# OpenEVSE_PLUS_v2_1.net
KiCad netlist of a schematic drawn in EAGLE
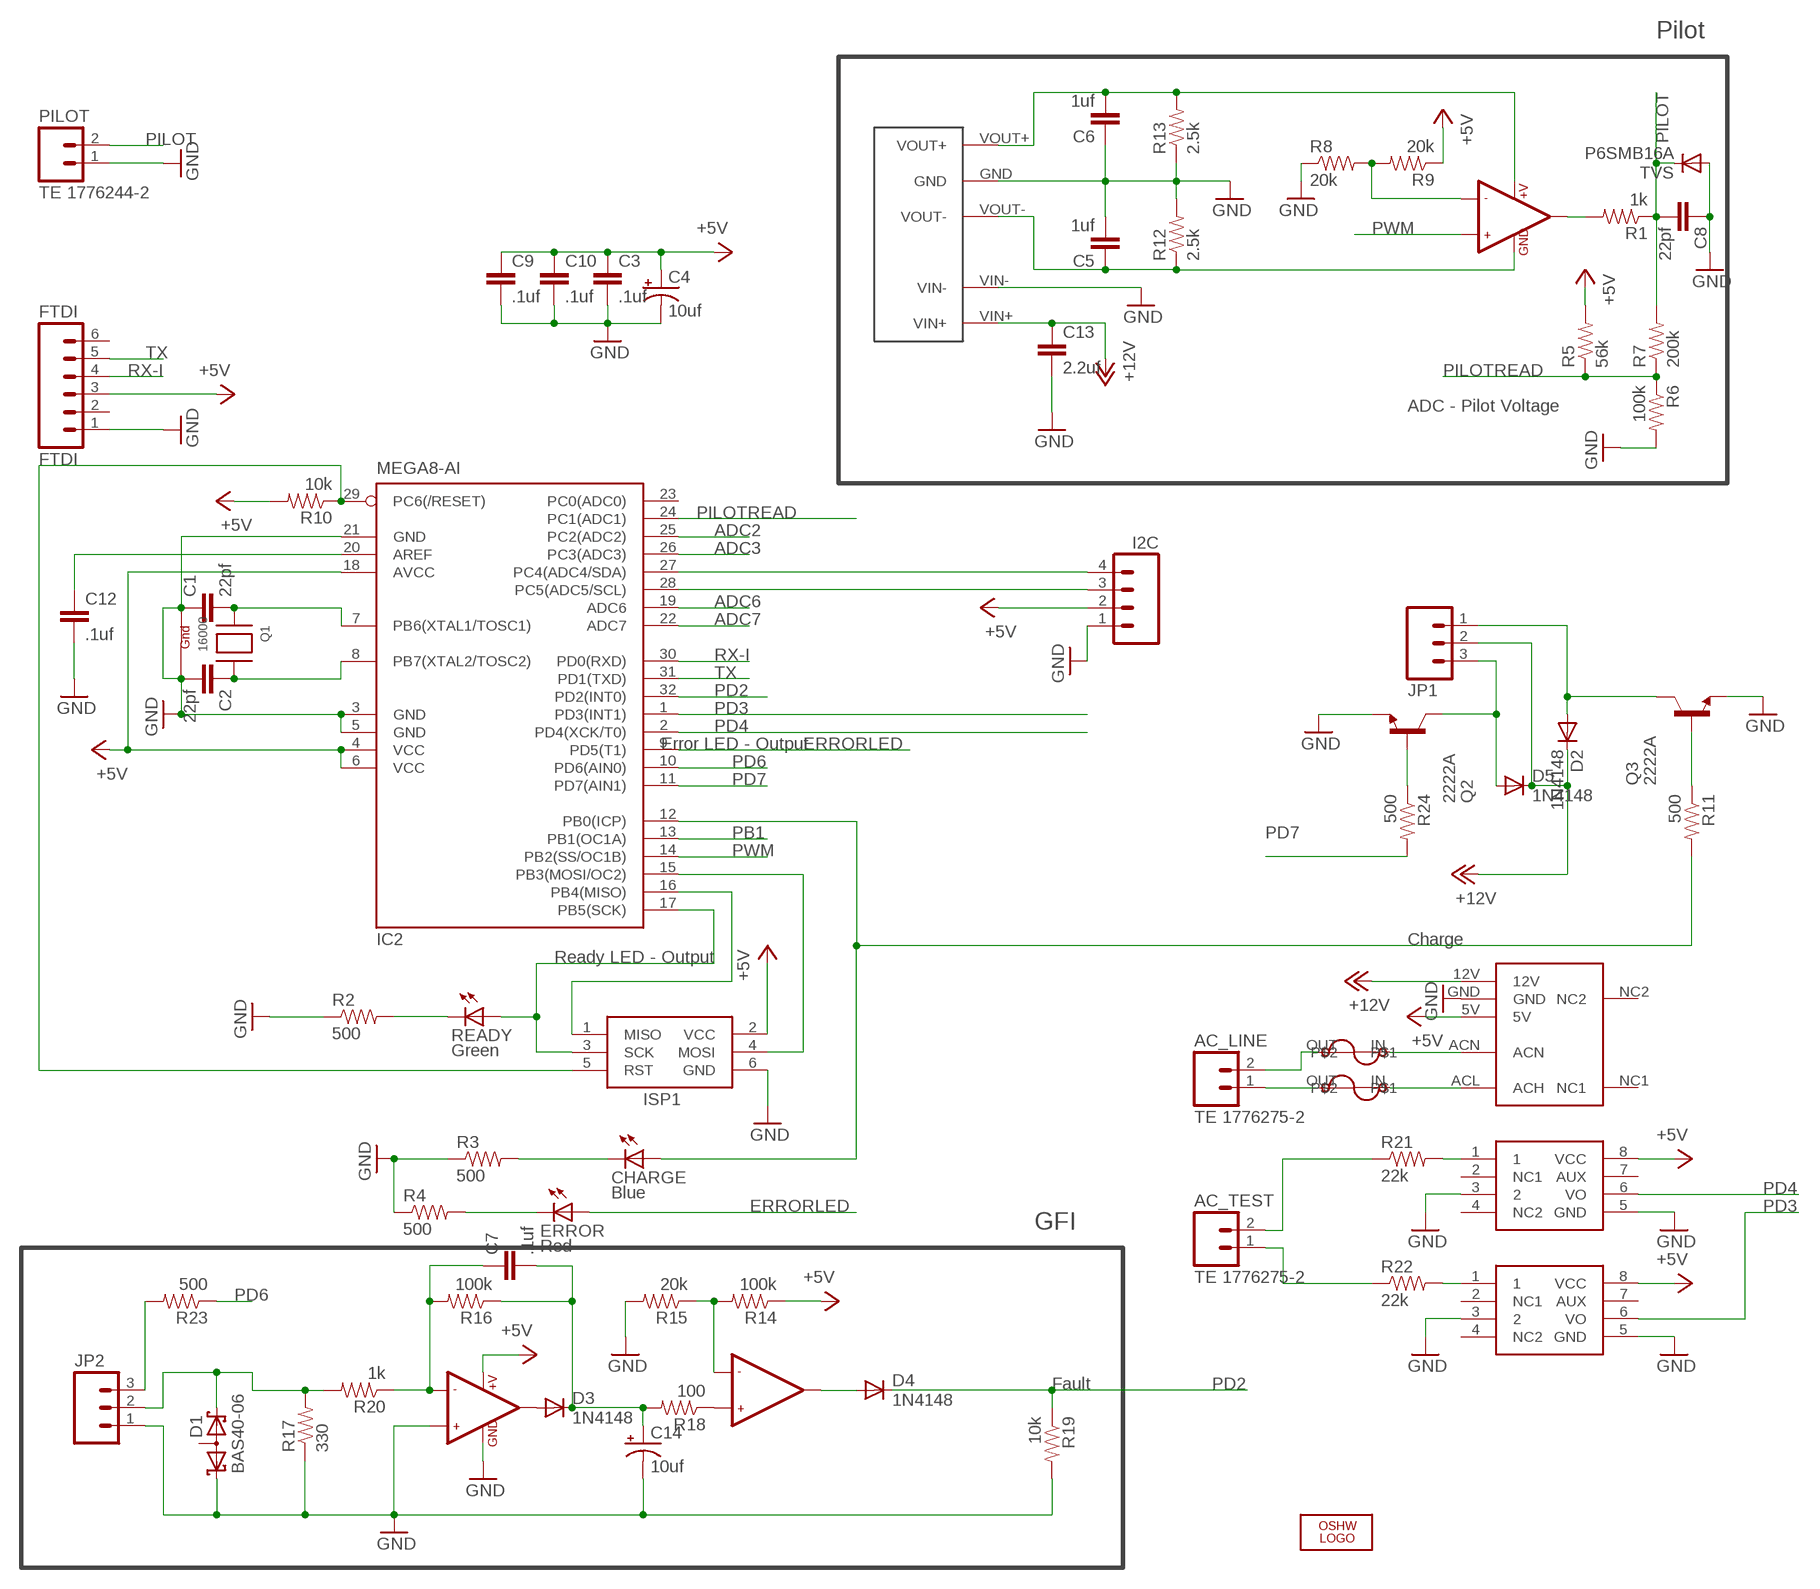
[diagram p0: schematic, sheet 1]

(export (version "E")
  (design (tool "Eeschema 10.0.6"))
  (components
    (comp (ref "AC_LINE")
      (value "TE 1776275-2")
      (footprint "eagle-import:SCREWTERMINAL-3.5MM-2_LOCK")
      (libsource (lib "eagle-import") (part "M023.5MM_LOCK"))
    )
    (comp (ref "AC_TEST")
      (value "TE 1776275-2")
      (footprint "eagle-import:SCREWTERMINAL-3.5MM-2_LOCK")
      (libsource (lib "eagle-import") (part "M023.5MM_LOCK"))
    )
    (comp (ref "C1")
      (value "22pf")
      (footprint "eagle-import:0805")
      (libsource (lib "eagle-import") (part "CAP0805"))
    )
    (comp (ref "C2")
      (value "22pf")
      (footprint "eagle-import:0805")
      (libsource (lib "eagle-import") (part "CAP0805"))
    )
    (comp (ref "C3")
      (value ".1uf")
      (footprint "eagle-import:0805")
      (libsource (lib "eagle-import") (part "CAP0805"))
    )
    (comp (ref "C4")
      (value "10uf")
      (footprint "eagle-import:EIA3216")
      (libsource (lib "eagle-import") (part "CAP_POL1206"))
    )
    (comp (ref "C5")
      (value "1uf")
      (footprint "eagle-import:0805")
      (libsource (lib "eagle-import") (part "CAP0805"))
    )
    (comp (ref "C6")
      (value "1uf")
      (footprint "eagle-import:0805")
      (libsource (lib "eagle-import") (part "CAP0805"))
    )
    (comp (ref "C7")
      (value ".1uf")
      (footprint "eagle-import:0805")
      (libsource (lib "eagle-import") (part "CAP0805"))
    )
    (comp (ref "C8")
      (value "22pf")
      (footprint "eagle-import:0805")
      (libsource (lib "eagle-import") (part "CAP0805"))
    )
    (comp (ref "C9")
      (value ".1uf")
      (footprint "eagle-import:0805")
      (libsource (lib "eagle-import") (part "CAP0805"))
    )
    (comp (ref "C10")
      (value ".1uf")
      (footprint "eagle-import:0805")
      (libsource (lib "eagle-import") (part "CAP0805"))
    )
    (comp (ref "C12")
      (value ".1uf")
      (footprint "eagle-import:0805")
      (libsource (lib "eagle-import") (part "CAP0805"))
    )
    (comp (ref "C13")
      (value "2.2uf")
      (footprint "eagle-import:0805")
      (libsource (lib "eagle-import") (part "CAP0805"))
    )
    (comp (ref "C14")
      (value "10uf")
      (footprint "eagle-import:EIA3216")
      (libsource (lib "eagle-import") (part "CAP_POL1206"))
    )
    (comp (ref "CHARGE")
      (value "Blue")
      (footprint "eagle-import:LED-0603")
      (libsource (lib "eagle-import") (part "LED0603"))
    )
    (comp (ref "D1")
      (value "BAS40-06")
      (footprint "eagle-import:SOT23")
      (libsource (lib "eagle-import") (part "BAS40-06"))
    )
    (comp (ref "D2")
      (value "1N4148")
      (footprint "eagle-import:SOD123")
      (libsource (lib "eagle-import") (part "DIODE-SOD123"))
    )
    (comp (ref "D3")
      (value "1N4148")
      (footprint "eagle-import:SOD123")
      (libsource (lib "eagle-import") (part "DIODE-SOD123"))
    )
    (comp (ref "D4")
      (value "1N4148")
      (footprint "eagle-import:SOD123")
      (libsource (lib "eagle-import") (part "DIODE-SOD123"))
    )
    (comp (ref "D5")
      (value "1N4148")
      (footprint "eagle-import:SOD123")
      (libsource (lib "eagle-import") (part "DIODE-SOD123"))
    )
    (comp (ref "DCDC")
      (value "D107E")
      (footprint "eagle-import:DCDC_SIP")
      (libsource (lib "eagle-import") (part "DCDC_SIP"))
    )
    (comp (ref "ERROR")
      (value "Red")
      (footprint "eagle-import:LED-0603")
      (libsource (lib "eagle-import") (part "LED0603"))
    )
    (comp (ref "FTDI")
      (value "FTDI")
      (footprint "eagle-import:1X06_LOCK")
      (libsource (lib "eagle-import") (part "M06LOCK"))
    )
    (comp (ref "I2C")
      (value "M04LOCK")
      (footprint "eagle-import:1X04_LOCK")
      (libsource (lib "eagle-import") (part "M04LOCK"))
    )
    (comp (ref "IC1")
      (value "MID400")
      (footprint "eagle-import:DIP08")
      (libsource (lib "eagle-import") (part "MID400"))
    )
    (comp (ref "IC2")
      (value "MEGA8-AI")
      (footprint "eagle-import:TQFP32-08")
      (fields (field (name "MPN") "ATMEGA8-16AU"))
      (libsource (lib "eagle-import") (part "MEGA8-AI"))
    )
    (comp (ref "IC3")
      (value "LMV358")
      (footprint "eagle-import:SO08")
      (libsource (lib "eagle-import") (part "LMV358"))
    )
    (comp (ref "IC4")
      (value "LMV358")
      (footprint "eagle-import:SO08")
      (libsource (lib "eagle-import") (part "LMV358"))
    )
    (comp (ref "IC5")
      (value "MID400")
      (footprint "eagle-import:DIP08")
      (libsource (lib "eagle-import") (part "MID400"))
    )
    (comp (ref "ISP1")
      (value "AVRISP-6")
      (footprint "eagle-import:AVRISP")
      (libsource (lib "eagle-import") (part "AVRISP-6"))
    )
    (comp (ref "JP1")
      (value "M03SCREW_LOCK")
      (footprint "eagle-import:SCREWTERMINAL-3.5MM-3_LOCK.007S")
      (libsource (lib "eagle-import") (part "M03SCREW_LOCK"))
    )
    (comp (ref "JP2")
      (value "M03LOCK")
      (footprint "eagle-import:1X03_LOCK")
      (libsource (lib "eagle-import") (part "M03LOCK"))
    )
    (comp (ref "LOGO1")
      (value "OSHW_LOGO_8MILX0150-NT")
      (footprint "eagle-import:OSHW_8X150_NOTEXT")
      (libsource (lib "eagle-import") (part "OSHW_LOGO_8MILX0150-NT"))
    )
    (comp (ref "PILOT")
      (value "TE 1776244-2")
      (footprint "eagle-import:SCREWTERMINAL-5MM-2")
      (libsource (lib "eagle-import") (part "M025MM"))
    )
    (comp (ref "Q1")
      (value "16000")
      (footprint "eagle-import:NX3225")
      (libsource (lib "eagle-import") (part "XTAL-4-3225"))
    )
    (comp (ref "Q2")
      (value "2222A")
      (footprint "eagle-import:SOT23")
      (libsource (lib "eagle-import") (part "BCX70SMD"))
    )
    (comp (ref "Q3")
      (value "2222A")
      (footprint "eagle-import:SOT23")
      (libsource (lib "eagle-import") (part "BCX70SMD"))
    )
    (comp (ref "R1")
      (value "1k")
      (footprint "eagle-import:0805")
      (libsource (lib "eagle-import") (part "RESISTOR0805-RES"))
    )
    (comp (ref "R2")
      (value "500")
      (footprint "eagle-import:0805")
      (libsource (lib "eagle-import") (part "RESISTOR0805-RES"))
    )
    (comp (ref "R3")
      (value "500")
      (footprint "eagle-import:0805")
      (libsource (lib "eagle-import") (part "RESISTOR0805-RES"))
    )
    (comp (ref "R4")
      (value "500")
      (footprint "eagle-import:0805")
      (libsource (lib "eagle-import") (part "RESISTOR0805-RES"))
    )
    (comp (ref "R5")
      (value "56k")
      (footprint "eagle-import:0805")
      (libsource (lib "eagle-import") (part "RESISTOR0805-RES"))
    )
    (comp (ref "R6")
      (value "100k")
      (footprint "eagle-import:0805")
      (libsource (lib "eagle-import") (part "RESISTOR0805-RES"))
    )
    (comp (ref "R7")
      (value "200k")
      (footprint "eagle-import:0805")
      (libsource (lib "eagle-import") (part "RESISTOR0805-RES"))
    )
    (comp (ref "R8")
      (value "20k")
      (footprint "eagle-import:0805")
      (libsource (lib "eagle-import") (part "RESISTOR0805-RES"))
    )
    (comp (ref "R9")
      (value "20k")
      (footprint "eagle-import:0805")
      (libsource (lib "eagle-import") (part "RESISTOR0805-RES"))
    )
    (comp (ref "R10")
      (value "10k")
      (footprint "eagle-import:0805")
      (libsource (lib "eagle-import") (part "RESISTOR0805-RES"))
    )
    (comp (ref "R11")
      (value "500")
      (footprint "eagle-import:0805")
      (libsource (lib "eagle-import") (part "RESISTOR0805-RES"))
    )
    (comp (ref "R12")
      (value "2.5k")
      (footprint "eagle-import:0805")
      (libsource (lib "eagle-import") (part "RESISTOR0805-RES"))
    )
    (comp (ref "R13")
      (value "2.5k")
      (footprint "eagle-import:0805")
      (libsource (lib "eagle-import") (part "RESISTOR0805-RES"))
    )
    (comp (ref "R14")
      (value "100k")
      (footprint "eagle-import:0805")
      (libsource (lib "eagle-import") (part "RESISTOR0805-RES"))
    )
    (comp (ref "R15")
      (value "20k")
      (footprint "eagle-import:0805")
      (libsource (lib "eagle-import") (part "RESISTOR0805-RES"))
    )
    (comp (ref "R16")
      (value "100k")
      (footprint "eagle-import:0805")
      (libsource (lib "eagle-import") (part "RESISTOR0805-RES"))
    )
    (comp (ref "R17")
      (value "330")
      (footprint "eagle-import:0805")
      (libsource (lib "eagle-import") (part "RESISTOR0805-RES"))
    )
    (comp (ref "R18")
      (value "100")
      (footprint "eagle-import:0805")
      (libsource (lib "eagle-import") (part "RESISTOR0805-RES"))
    )
    (comp (ref "R19")
      (value "10k")
      (footprint "eagle-import:0805")
      (libsource (lib "eagle-import") (part "RESISTOR0805-RES"))
    )
    (comp (ref "R20")
      (value "1k")
      (footprint "eagle-import:0805")
      (libsource (lib "eagle-import") (part "RESISTOR0805-RES"))
    )
    (comp (ref "R21")
      (value "22k")
      (footprint "eagle-import:AXIAL-0.4")
      (libsource (lib "eagle-import") (part "RESISTORPTH-1/4W"))
    )
    (comp (ref "R22")
      (value "22k")
      (footprint "eagle-import:AXIAL-0.4")
      (libsource (lib "eagle-import") (part "RESISTORPTH-1/4W"))
    )
    (comp (ref "R23")
      (value "500")
      (footprint "eagle-import:0805")
      (libsource (lib "eagle-import") (part "RESISTOR0805-RES"))
    )
    (comp (ref "R24")
      (value "500")
      (footprint "eagle-import:0805")
      (libsource (lib "eagle-import") (part "RESISTOR0805-RES"))
    )
    (comp (ref "READY")
      (value "Green")
      (footprint "eagle-import:LED-0603")
      (libsource (lib "eagle-import") (part "LED0603"))
    )
    (comp (ref "TVS")
      (value "P6SMB16A")
      (footprint "eagle-import:SMB")
      (libsource (lib "eagle-import") (part "DIODE-SMB"))
    )
    (comp (ref "U$1")
      (value "MPM-04E-1205")
      (footprint "eagle-import:MPM-04E-1205")
      (libsource (lib "eagle-import") (part "MPM-04E-1205"))
    )
    (comp (ref "U$2")
      (value "BEL1AFUSE")
      (footprint "eagle-import:BELFUSE1A")
      (libsource (lib "eagle-import") (part "BEL1AFUSE"))
    )
    (comp (ref "U$5")
      (value "BEL1AFUSE")
      (footprint "eagle-import:BELFUSE1A")
      (libsource (lib "eagle-import") (part "BEL1AFUSE"))
    )
  )
  (nets
    (net (code "1") (name "+5V") (class "Default")
      (node (ref "C10") (pin "1") (pinfunction "1_1") (pintype "passive"))
      (node (ref "C3") (pin "1") (pinfunction "1_1") (pintype "passive"))
      (node (ref "C4") (pin "A") (pinfunction "+_A") (pintype "passive"))
      (node (ref "C9") (pin "1") (pinfunction "1_1") (pintype "passive"))
      (node (ref "FTDI") (pin "3") (pinfunction "3_3") (pintype "passive"))
      (node (ref "I2C") (pin "2") (pinfunction "2_2") (pintype "passive"))
      (node (ref "IC1") (pin "8") (pinfunction "VCC_8") (pintype "bidirectional"))
      (node (ref "IC2") (pin "18") (pinfunction "AVCC_18") (pintype "power_in"))
      (node (ref "IC2") (pin "4") (pinfunction "VCC_4") (pintype "power_in"))
      (node (ref "IC2") (pin "6") (pinfunction "VCC_6") (pintype "power_in"))
      (node (ref "IC3") (pin "8") (pinfunction "+V_8") (pintype "power_in"))
      (node (ref "IC5") (pin "8") (pinfunction "VCC_8") (pintype "bidirectional"))
      (node (ref "ISP1") (pin "2") (pinfunction "VCC_2") (pintype "power_in"))
      (node (ref "R10") (pin "2") (pinfunction "2_2") (pintype "passive"))
      (node (ref "R14") (pin "1") (pinfunction "1_1") (pintype "passive"))
      (node (ref "R5") (pin "2") (pinfunction "2_2") (pintype "passive"))
      (node (ref "R9") (pin "1") (pinfunction "1_1") (pintype "passive"))
      (node (ref "U$1") (pin "5V") (pinfunction "5V_5V") (pintype "bidirectional"))
    )
    (net (code "2") (name "+12V") (class "Default")
      (node (ref "C13") (pin "1") (pinfunction "1_1") (pintype "passive"))
      (node (ref "D2") (pin "C") (pinfunction "C_C") (pintype "passive"))
      (node (ref "D5") (pin "C") (pinfunction "C_C") (pintype "passive"))
      (node (ref "DCDC") (pin "VIN+") (pinfunction "VIN+_VIN+") (pintype "bidirectional"))
      (node (ref "JP1") (pin "2") (pinfunction "2_2") (pintype "passive"))
      (node (ref "U$1") (pin "12V") (pinfunction "12V_12V") (pintype "bidirectional"))
    )
    (net (code "3") (name "/ADC2") (class "Default")
      (node (ref "IC2") (pin "25") (pinfunction "PC2(ADC2)_25") (pintype "bidirectional"))
    )
    (net (code "4") (name "/ADC3") (class "Default")
      (node (ref "IC2") (pin "26") (pinfunction "PC3(ADC3)_26") (pintype "bidirectional"))
    )
    (net (code "5") (name "/ADC6") (class "Default")
      (node (ref "IC2") (pin "19") (pinfunction "ADC6_19") (pintype "bidirectional"))
    )
    (net (code "6") (name "/ADC7") (class "Default")
      (node (ref "IC2") (pin "22") (pinfunction "ADC7_22") (pintype "bidirectional"))
    )
    (net (code "7") (name "/ERRORLED") (class "Default")
      (node (ref "ERROR") (pin "A") (pinfunction "A_A") (pintype "passive"))
      (node (ref "IC2") (pin "9") (pinfunction "PD5(T1)_9") (pintype "bidirectional"))
    )
    (net (code "8") (name "/PB1") (class "Default")
      (node (ref "IC2") (pin "13") (pinfunction "PB1(OC1A)_13") (pintype "bidirectional"))
    )
    (net (code "9") (name "/PD2") (class "Default")
      (node (ref "D4") (pin "C") (pinfunction "C_C") (pintype "passive"))
      (node (ref "IC2") (pin "32") (pinfunction "PD2(INT0)_32") (pintype "bidirectional"))
      (node (ref "R19") (pin "1") (pinfunction "1_1") (pintype "passive"))
    )
    (net (code "10") (name "/PD3") (class "Default")
      (node (ref "IC2") (pin "1") (pinfunction "PD3(INT1)_1") (pintype "bidirectional"))
      (node (ref "IC5") (pin "6") (pinfunction "VO_6") (pintype "bidirectional"))
    )
    (net (code "11") (name "/PD4") (class "Default")
      (node (ref "IC1") (pin "6") (pinfunction "VO_6") (pintype "bidirectional"))
      (node (ref "IC2") (pin "2") (pinfunction "PD4(XCK/T0)_2") (pintype "bidirectional"))
    )
    (net (code "12") (name "/PD6") (class "Default")
      (node (ref "IC2") (pin "10") (pinfunction "PD6(AIN0)_10") (pintype "bidirectional"))
      (node (ref "R23") (pin "1") (pinfunction "1_1") (pintype "passive"))
    )
    (net (code "13") (name "/PD7") (class "Default")
      (node (ref "IC2") (pin "11") (pinfunction "PD7(AIN1)_11") (pintype "bidirectional"))
      (node (ref "R24") (pin "2") (pinfunction "2_2") (pintype "passive"))
    )
    (net (code "14") (name "/PILOT") (class "Default")
      (node (ref "C8") (pin "2") (pinfunction "2_2") (pintype "passive"))
      (node (ref "PILOT") (pin "2") (pinfunction "2_2") (pintype "passive"))
      (node (ref "R1") (pin "1") (pinfunction "1_1") (pintype "passive"))
      (node (ref "R7") (pin "2") (pinfunction "2_2") (pintype "passive"))
      (node (ref "TVS") (pin "C") (pinfunction "C_C") (pintype "passive"))
    )
    (net (code "15") (name "/PILOTREAD") (class "Default")
      (node (ref "IC2") (pin "24") (pinfunction "PC1(ADC1)_24") (pintype "bidirectional"))
      (node (ref "R5") (pin "1") (pinfunction "1_1") (pintype "passive"))
      (node (ref "R6") (pin "1") (pinfunction "1_1") (pintype "passive"))
      (node (ref "R7") (pin "1") (pinfunction "1_1") (pintype "passive"))
    )
    (net (code "16") (name "/PWM") (class "Default")
      (node (ref "IC2") (pin "14") (pinfunction "PB2(SS/OC1B)_14") (pintype "bidirectional"))
      (node (ref "IC4") (pin "3") (pinfunction "+IN1_3") (pintype "input"))
    )
    (net (code "17") (name "/RX-I") (class "Default")
      (node (ref "FTDI") (pin "4") (pinfunction "4_4") (pintype "passive"))
      (node (ref "IC2") (pin "30") (pinfunction "PD0(RXD)_30") (pintype "bidirectional"))
    )
    (net (code "18") (name "/TX") (class "Default")
      (node (ref "FTDI") (pin "5") (pinfunction "5_5") (pintype "passive"))
      (node (ref "IC2") (pin "31") (pinfunction "PD1(TXD)_31") (pintype "bidirectional"))
    )
    (net (code "19") (name "GND") (class "Default")
      (node (ref "C1") (pin "1") (pinfunction "1_1") (pintype "passive"))
      (node (ref "C10") (pin "2") (pinfunction "2_2") (pintype "passive"))
      (node (ref "C12") (pin "2") (pinfunction "2_2") (pintype "passive"))
      (node (ref "C13") (pin "2") (pinfunction "2_2") (pintype "passive"))
      (node (ref "C14") (pin "C") (pinfunction "-_C") (pintype "passive"))
      (node (ref "C2") (pin "2") (pinfunction "2_2") (pintype "passive"))
      (node (ref "C3") (pin "2") (pinfunction "2_2") (pintype "passive"))
      (node (ref "C4") (pin "C") (pinfunction "-_C") (pintype "passive"))
      (node (ref "C5") (pin "2") (pinfunction "2_2") (pintype "passive"))
      (node (ref "C6") (pin "1") (pinfunction "1_1") (pintype "passive"))
      (node (ref "C8") (pin "1") (pinfunction "1_1") (pintype "passive"))
      (node (ref "C9") (pin "2") (pinfunction "2_2") (pintype "passive"))
      (node (ref "D1") (pin "1") (pinfunction "K1_1") (pintype "passive"))
      (node (ref "DCDC") (pin "GND") (pinfunction "GND_GND") (pintype "bidirectional"))
      (node (ref "DCDC") (pin "VIN-") (pinfunction "VIN-_VIN-") (pintype "bidirectional"))
      (node (ref "FTDI") (pin "1") (pinfunction "1_1") (pintype "passive"))
      (node (ref "I2C") (pin "1") (pinfunction "1_1") (pintype "passive"))
      (node (ref "IC1") (pin "3") (pinfunction "2_3") (pintype "bidirectional"))
      (node (ref "IC1") (pin "5") (pinfunction "GND_5") (pintype "bidirectional"))
      (node (ref "IC2") (pin "21") (pinfunction "GND_21") (pintype "power_in"))
      (node (ref "IC2") (pin "3") (pinfunction "GND_3") (pintype "power_in"))
      (node (ref "IC2") (pin "5") (pinfunction "GND_5") (pintype "power_in"))
      (node (ref "IC3") (pin "3") (pinfunction "+IN1_3") (pintype "input"))
      (node (ref "IC3") (pin "4") (pinfunction "GND_4") (pintype "power_in"))
      (node (ref "IC5") (pin "3") (pinfunction "2_3") (pintype "bidirectional"))
      (node (ref "IC5") (pin "5") (pinfunction "GND_5") (pintype "bidirectional"))
      (node (ref "ISP1") (pin "6") (pinfunction "GND_6") (pintype "power_in"))
      (node (ref "JP2") (pin "1") (pinfunction "1_1") (pintype "passive"))
      (node (ref "PILOT") (pin "1") (pinfunction "1_1") (pintype "passive"))
      (node (ref "Q1") (pin "1") (pinfunction "G1_1") (pintype "power_in"))
      (node (ref "Q1") (pin "3") (pinfunction "G2_3") (pintype "power_in"))
      (node (ref "Q2") (pin "2") (pinfunction "E_2") (pintype "passive"))
      (node (ref "Q3") (pin "2") (pinfunction "E_2") (pintype "passive"))
      (node (ref "R12") (pin "2") (pinfunction "2_2") (pintype "passive"))
      (node (ref "R13") (pin "1") (pinfunction "1_1") (pintype "passive"))
      (node (ref "R15") (pin "2") (pinfunction "2_2") (pintype "passive"))
      (node (ref "R17") (pin "1") (pinfunction "1_1") (pintype "passive"))
      (node (ref "R19") (pin "2") (pinfunction "2_2") (pintype "passive"))
      (node (ref "R2") (pin "1") (pinfunction "1_1") (pintype "passive"))
      (node (ref "R3") (pin "1") (pinfunction "1_1") (pintype "passive"))
      (node (ref "R4") (pin "1") (pinfunction "1_1") (pintype "passive"))
      (node (ref "R6") (pin "2") (pinfunction "2_2") (pintype "passive"))
      (node (ref "R8") (pin "1") (pinfunction "1_1") (pintype "passive"))
      (node (ref "TVS") (pin "A") (pinfunction "A_A") (pintype "passive"))
      (node (ref "U$1") (pin "GND") (pinfunction "GND_GND") (pintype "bidirectional"))
    )
    (net (code "20") (name "Net-(C14-+)") (class "Default")
      (node (ref "C14") (pin "A") (pinfunction "+_A") (pintype "passive"))
      (node (ref "C7") (pin "2") (pinfunction "2_2") (pintype "passive"))
      (node (ref "D3") (pin "C") (pinfunction "C_C") (pintype "passive"))
      (node (ref "R16") (pin "1") (pinfunction "1_1") (pintype "passive"))
      (node (ref "R18") (pin "2") (pinfunction "2_2") (pintype "passive"))
    )
    (net (code "21") (name "Net-(CHARGE-PadC)") (class "Default")
      (node (ref "CHARGE") (pin "C") (pinfunction "C_C") (pintype "passive"))
      (node (ref "R3") (pin "2") (pinfunction "2_2") (pintype "passive"))
    )
    (net (code "22") (name "Net-(D1-K2)") (class "Default")
      (node (ref "D1") (pin "2") (pinfunction "K2_2") (pintype "passive"))
      (node (ref "JP2") (pin "2") (pinfunction "2_2") (pintype "passive"))
      (node (ref "R17") (pin "2") (pinfunction "2_2") (pintype "passive"))
      (node (ref "R20") (pin "2") (pinfunction "2_2") (pintype "passive"))
    )
    (net (code "23") (name "Net-(ERROR-PadC)") (class "Default")
      (node (ref "ERROR") (pin "C") (pinfunction "C_C") (pintype "passive"))
      (node (ref "R4") (pin "2") (pinfunction "2_2") (pintype "passive"))
    )
    (net (code "24") (name "Net-(IC2-AREF)") (class "Default")
      (node (ref "C12") (pin "1") (pinfunction "1_1") (pintype "passive"))
      (node (ref "IC2") (pin "20") (pinfunction "AREF_20") (pintype "passive"))
    )
    (net (code "25") (name "Net-(IC2-PB0(ICP))") (class "Default")
      (node (ref "CHARGE") (pin "A") (pinfunction "A_A") (pintype "passive"))
      (node (ref "IC2") (pin "12") (pinfunction "PB0(ICP)_12") (pintype "bidirectional"))
      (node (ref "R11") (pin "2") (pinfunction "2_2") (pintype "passive"))
    )
    (net (code "26") (name "Net-(IC2-PB3(MOSI{slash}OC2))") (class "Default")
      (node (ref "IC2") (pin "15") (pinfunction "PB3(MOSI/OC2)_15") (pintype "bidirectional"))
      (node (ref "ISP1") (pin "4") (pinfunction "MOSI_4") (pintype "output"))
    )
    (net (code "27") (name "Net-(IC2-PB4(MISO))") (class "Default")
      (node (ref "IC2") (pin "16") (pinfunction "PB4(MISO)_16") (pintype "bidirectional"))
      (node (ref "ISP1") (pin "1") (pinfunction "MISO_1") (pintype "input"))
    )
    (net (code "28") (name "Net-(IC2-PB5(SCK))") (class "Default")
      (node (ref "IC2") (pin "17") (pinfunction "PB5(SCK)_17") (pintype "bidirectional"))
      (node (ref "ISP1") (pin "3") (pinfunction "SCK_3") (pintype "output"))
      (node (ref "READY") (pin "A") (pinfunction "A_A") (pintype "passive"))
    )
    (net (code "29") (name "Net-(IC2-PB6(XTAL1{slash}TOSC1))") (class "Default")
      (node (ref "C1") (pin "2") (pinfunction "2_2") (pintype "passive"))
      (node (ref "IC2") (pin "7") (pinfunction "PB6(XTAL1/TOSC1)_7") (pintype "bidirectional"))
      (node (ref "Q1") (pin "2") (pinfunction "X1_2") (pintype "bidirectional"))
    )
    (net (code "30") (name "Net-(IC2-PB7(XTAL2{slash}TOSC2))") (class "Default")
      (node (ref "C2") (pin "1") (pinfunction "1_1") (pintype "passive"))
      (node (ref "IC2") (pin "8") (pinfunction "PB7(XTAL2/TOSC2)_8") (pintype "bidirectional"))
      (node (ref "Q1") (pin "4") (pinfunction "X2_4") (pintype "bidirectional"))
    )
    (net (code "31") (name "Net-(IC2-PC4(ADC4{slash}SDA))") (class "Default")
      (node (ref "I2C") (pin "4") (pinfunction "4_4") (pintype "passive"))
      (node (ref "IC2") (pin "27") (pinfunction "PC4(ADC4/SDA)_27") (pintype "bidirectional"))
    )
    (net (code "32") (name "Net-(IC2-PC5(ADC5{slash}SCL))") (class "Default")
      (node (ref "I2C") (pin "3") (pinfunction "3_3") (pintype "passive"))
      (node (ref "IC2") (pin "28") (pinfunction "PC5(ADC5/SCL)_28") (pintype "bidirectional"))
    )
    (net (code "33") (name "Net-(IC2-PC6({slash}RESET))") (class "Default")
      (node (ref "IC2") (pin "29") (pinfunction "PC6(/RESET)_29") (pintype "bidirectional"))
      (node (ref "ISP1") (pin "5") (pinfunction "RST_5") (pintype "output"))
      (node (ref "R10") (pin "1") (pinfunction "1_1") (pintype "passive"))
    )
    (net (code "34") (name "Net-(IC3A--IN1)") (class "Default")
      (node (ref "C7") (pin "1") (pinfunction "1_1") (pintype "passive"))
      (node (ref "IC3") (pin "2") (pinfunction "-IN1_2") (pintype "input"))
      (node (ref "R16") (pin "2") (pinfunction "2_2") (pintype "passive"))
      (node (ref "R20") (pin "1") (pinfunction "1_1") (pintype "passive"))
    )
    (net (code "35") (name "Net-(IC3A-OUT1)") (class "Default")
      (node (ref "D3") (pin "A") (pinfunction "A_A") (pintype "passive"))
      (node (ref "IC3") (pin "1") (pinfunction "OUT1_1") (pintype "output"))
    )
    (net (code "36") (name "Net-(IC3B-+IN2)") (class "Default")
      (node (ref "IC3") (pin "5") (pinfunction "+IN2_5") (pintype "input"))
      (node (ref "R18") (pin "1") (pinfunction "1_1") (pintype "passive"))
    )
    (net (code "37") (name "Net-(IC3B--IN2)") (class "Default")
      (node (ref "IC3") (pin "6") (pinfunction "-IN2_6") (pintype "input"))
      (node (ref "R14") (pin "2") (pinfunction "2_2") (pintype "passive"))
      (node (ref "R15") (pin "1") (pinfunction "1_1") (pintype "passive"))
    )
    (net (code "38") (name "Net-(IC3B-OUT2)") (class "Default")
      (node (ref "D4") (pin "A") (pinfunction "A_A") (pintype "passive"))
      (node (ref "IC3") (pin "7") (pinfunction "OUT2_7") (pintype "output"))
    )
    (net (code "39") (name "Net-(IC4A-+V)") (class "Default")
      (node (ref "C6") (pin "2") (pinfunction "2_2") (pintype "passive"))
      (node (ref "DCDC") (pin "VOUT+") (pinfunction "VOUT+_VOUT+") (pintype "bidirectional"))
      (node (ref "IC4") (pin "8") (pinfunction "+V_8") (pintype "power_in"))
      (node (ref "R13") (pin "2") (pinfunction "2_2") (pintype "passive"))
    )
    (net (code "40") (name "Net-(IC4A--IN1)") (class "Default")
      (node (ref "IC4") (pin "2") (pinfunction "-IN1_2") (pintype "input"))
      (node (ref "R8") (pin "2") (pinfunction "2_2") (pintype "passive"))
      (node (ref "R9") (pin "2") (pinfunction "2_2") (pintype "passive"))
    )
    (net (code "41") (name "Net-(IC4A-GND)") (class "Default")
      (node (ref "C5") (pin "1") (pinfunction "1_1") (pintype "passive"))
      (node (ref "DCDC") (pin "VOUT-") (pinfunction "VOUT-_VOUT-") (pintype "bidirectional"))
      (node (ref "IC4") (pin "4") (pinfunction "GND_4") (pintype "power_in"))
      (node (ref "R12") (pin "1") (pinfunction "1_1") (pintype "passive"))
    )
    (net (code "42") (name "Net-(IC4A-OUT1)") (class "Default")
      (node (ref "IC4") (pin "1") (pinfunction "OUT1_1") (pintype "output"))
      (node (ref "R1") (pin "2") (pinfunction "2_2") (pintype "passive"))
    )
    (net (code "43") (name "Net-(JP2-Pad3)") (class "Default")
      (node (ref "JP2") (pin "3") (pinfunction "3_3") (pintype "passive"))
      (node (ref "R23") (pin "2") (pinfunction "2_2") (pintype "passive"))
    )
    (net (code "44") (name "Net-(Q2-B)") (class "Default")
      (node (ref "Q2") (pin "1") (pinfunction "B_1") (pintype "passive"))
      (node (ref "R24") (pin "1") (pinfunction "1_1") (pintype "passive"))
    )
    (net (code "45") (name "Net-(Q2-C)") (class "Default")
      (node (ref "D5") (pin "A") (pinfunction "A_A") (pintype "passive"))
      (node (ref "JP1") (pin "3") (pinfunction "3_3") (pintype "passive"))
      (node (ref "Q2") (pin "3") (pinfunction "C_3") (pintype "passive"))
    )
    (net (code "46") (name "Net-(Q3-B)") (class "Default")
      (node (ref "Q3") (pin "1") (pinfunction "B_1") (pintype "passive"))
      (node (ref "R11") (pin "1") (pinfunction "1_1") (pintype "passive"))
    )
    (net (code "47") (name "Net-(Q3-C)") (class "Default")
      (node (ref "D2") (pin "A") (pinfunction "A_A") (pintype "passive"))
      (node (ref "JP1") (pin "1") (pinfunction "1_1") (pintype "passive"))
      (node (ref "Q3") (pin "3") (pinfunction "C_3") (pintype "passive"))
    )
    (net (code "48") (name "Net-(R2-Pad2)") (class "Default")
      (node (ref "R2") (pin "2") (pinfunction "2_2") (pintype "passive"))
      (node (ref "READY") (pin "C") (pinfunction "C_C") (pintype "passive"))
    )
    (net (code "49") (name "Net-(R21-1)") (class "Default")
      (node (ref "AC_TEST") (pin "2") (pinfunction "2_2") (pintype "passive"))
      (node (ref "R21") (pin "P$1") (pinfunction "1_P$1") (pintype "passive"))
    )
    (net (code "50") (name "Net-(R21-2)") (class "Default")
      (node (ref "IC1") (pin "1") (pinfunction "1_1") (pintype "bidirectional"))
      (node (ref "R21") (pin "P$2") (pinfunction "2_P$2") (pintype "passive"))
    )
    (net (code "51") (name "Net-(R22-1)") (class "Default")
      (node (ref "AC_TEST") (pin "1") (pinfunction "1_1") (pintype "passive"))
      (node (ref "R22") (pin "P$1") (pinfunction "1_P$1") (pintype "passive"))
    )
    (net (code "52") (name "Net-(R22-2)") (class "Default")
      (node (ref "IC5") (pin "1") (pinfunction "1_1") (pintype "bidirectional"))
      (node (ref "R22") (pin "P$2") (pinfunction "2_P$2") (pintype "passive"))
    )
    (net (code "53") (name "Net-(U$1-ACH)") (class "Default")
      (node (ref "U$1") (pin "ACL") (pinfunction "ACH_ACL") (pintype "bidirectional"))
      (node (ref "U$2") (pin "IN") (pinfunction "P$2_IN") (pintype "bidirectional"))
    )
    (net (code "54") (name "Net-(U$2-P$1)") (class "Default")
      (node (ref "AC_LINE") (pin "1") (pinfunction "1_1") (pintype "passive"))
      (node (ref "U$2") (pin "OUT") (pinfunction "P$1_OUT") (pintype "bidirectional"))
    )
    (net (code "55") (name "Net-(U$5-P$1)") (class "Default")
      (node (ref "AC_LINE") (pin "2") (pinfunction "2_2") (pintype "passive"))
      (node (ref "U$5") (pin "OUT") (pinfunction "P$1_OUT") (pintype "bidirectional"))
    )
    (net (code "56") (name "Net-(U$5-P$2)") (class "Default")
      (node (ref "U$1") (pin "ACN") (pinfunction "ACN_ACN") (pintype "bidirectional"))
      (node (ref "U$5") (pin "IN") (pinfunction "P$2_IN") (pintype "bidirectional"))
    )
    (net (code "57") (name "unconnected-(D1-AA-Pad3)") (class "Default")
      (node (ref "D1") (pin "3") (pinfunction "AA_3") (pintype "passive"))
    )
    (net (code "58") (name "unconnected-(FTDI-Pad2)") (class "Default")
      (node (ref "FTDI") (pin "2") (pinfunction "2_2") (pintype "passive"))
    )
    (net (code "59") (name "unconnected-(FTDI-Pad6)") (class "Default")
      (node (ref "FTDI") (pin "6") (pinfunction "6_6") (pintype "passive"))
    )
    (net (code "60") (name "unconnected-(IC1-AUX-Pad7)") (class "Default")
      (node (ref "IC1") (pin "7") (pinfunction "AUX_7") (pintype "bidirectional"))
    )
    (net (code "61") (name "unconnected-(IC1-NC1-Pad2)") (class "Default")
      (node (ref "IC1") (pin "2") (pinfunction "NC1_2") (pintype "bidirectional"))
    )
    (net (code "62") (name "unconnected-(IC1-NC2-Pad4)") (class "Default")
      (node (ref "IC1") (pin "4") (pinfunction "NC2_4") (pintype "bidirectional"))
    )
    (net (code "63") (name "unconnected-(IC2-PC0(ADC0)-Pad23)") (class "Default")
      (node (ref "IC2") (pin "23") (pinfunction "PC0(ADC0)_23") (pintype "bidirectional"))
    )
    (net (code "64") (name "unconnected-(IC5-AUX-Pad7)") (class "Default")
      (node (ref "IC5") (pin "7") (pinfunction "AUX_7") (pintype "bidirectional"))
    )
    (net (code "65") (name "unconnected-(IC5-NC1-Pad2)") (class "Default")
      (node (ref "IC5") (pin "2") (pinfunction "NC1_2") (pintype "bidirectional"))
    )
    (net (code "66") (name "unconnected-(IC5-NC2-Pad4)") (class "Default")
      (node (ref "IC5") (pin "4") (pinfunction "NC2_4") (pintype "bidirectional"))
    )
    (net (code "67") (name "unconnected-(U$1-PadNC1)") (class "Default")
      (node (ref "U$1") (pin "NC1") (pinfunction "NC1_NC1") (pintype "bidirectional"))
    )
    (net (code "68") (name "unconnected-(U$1-PadNC2)") (class "Default")
      (node (ref "U$1") (pin "NC2") (pinfunction "NC2_NC2") (pintype "bidirectional"))
    )
  )
)
